# Flexbus_Breakout.net
KiCad netlist of a schematic drawn in EasyEDA Pro
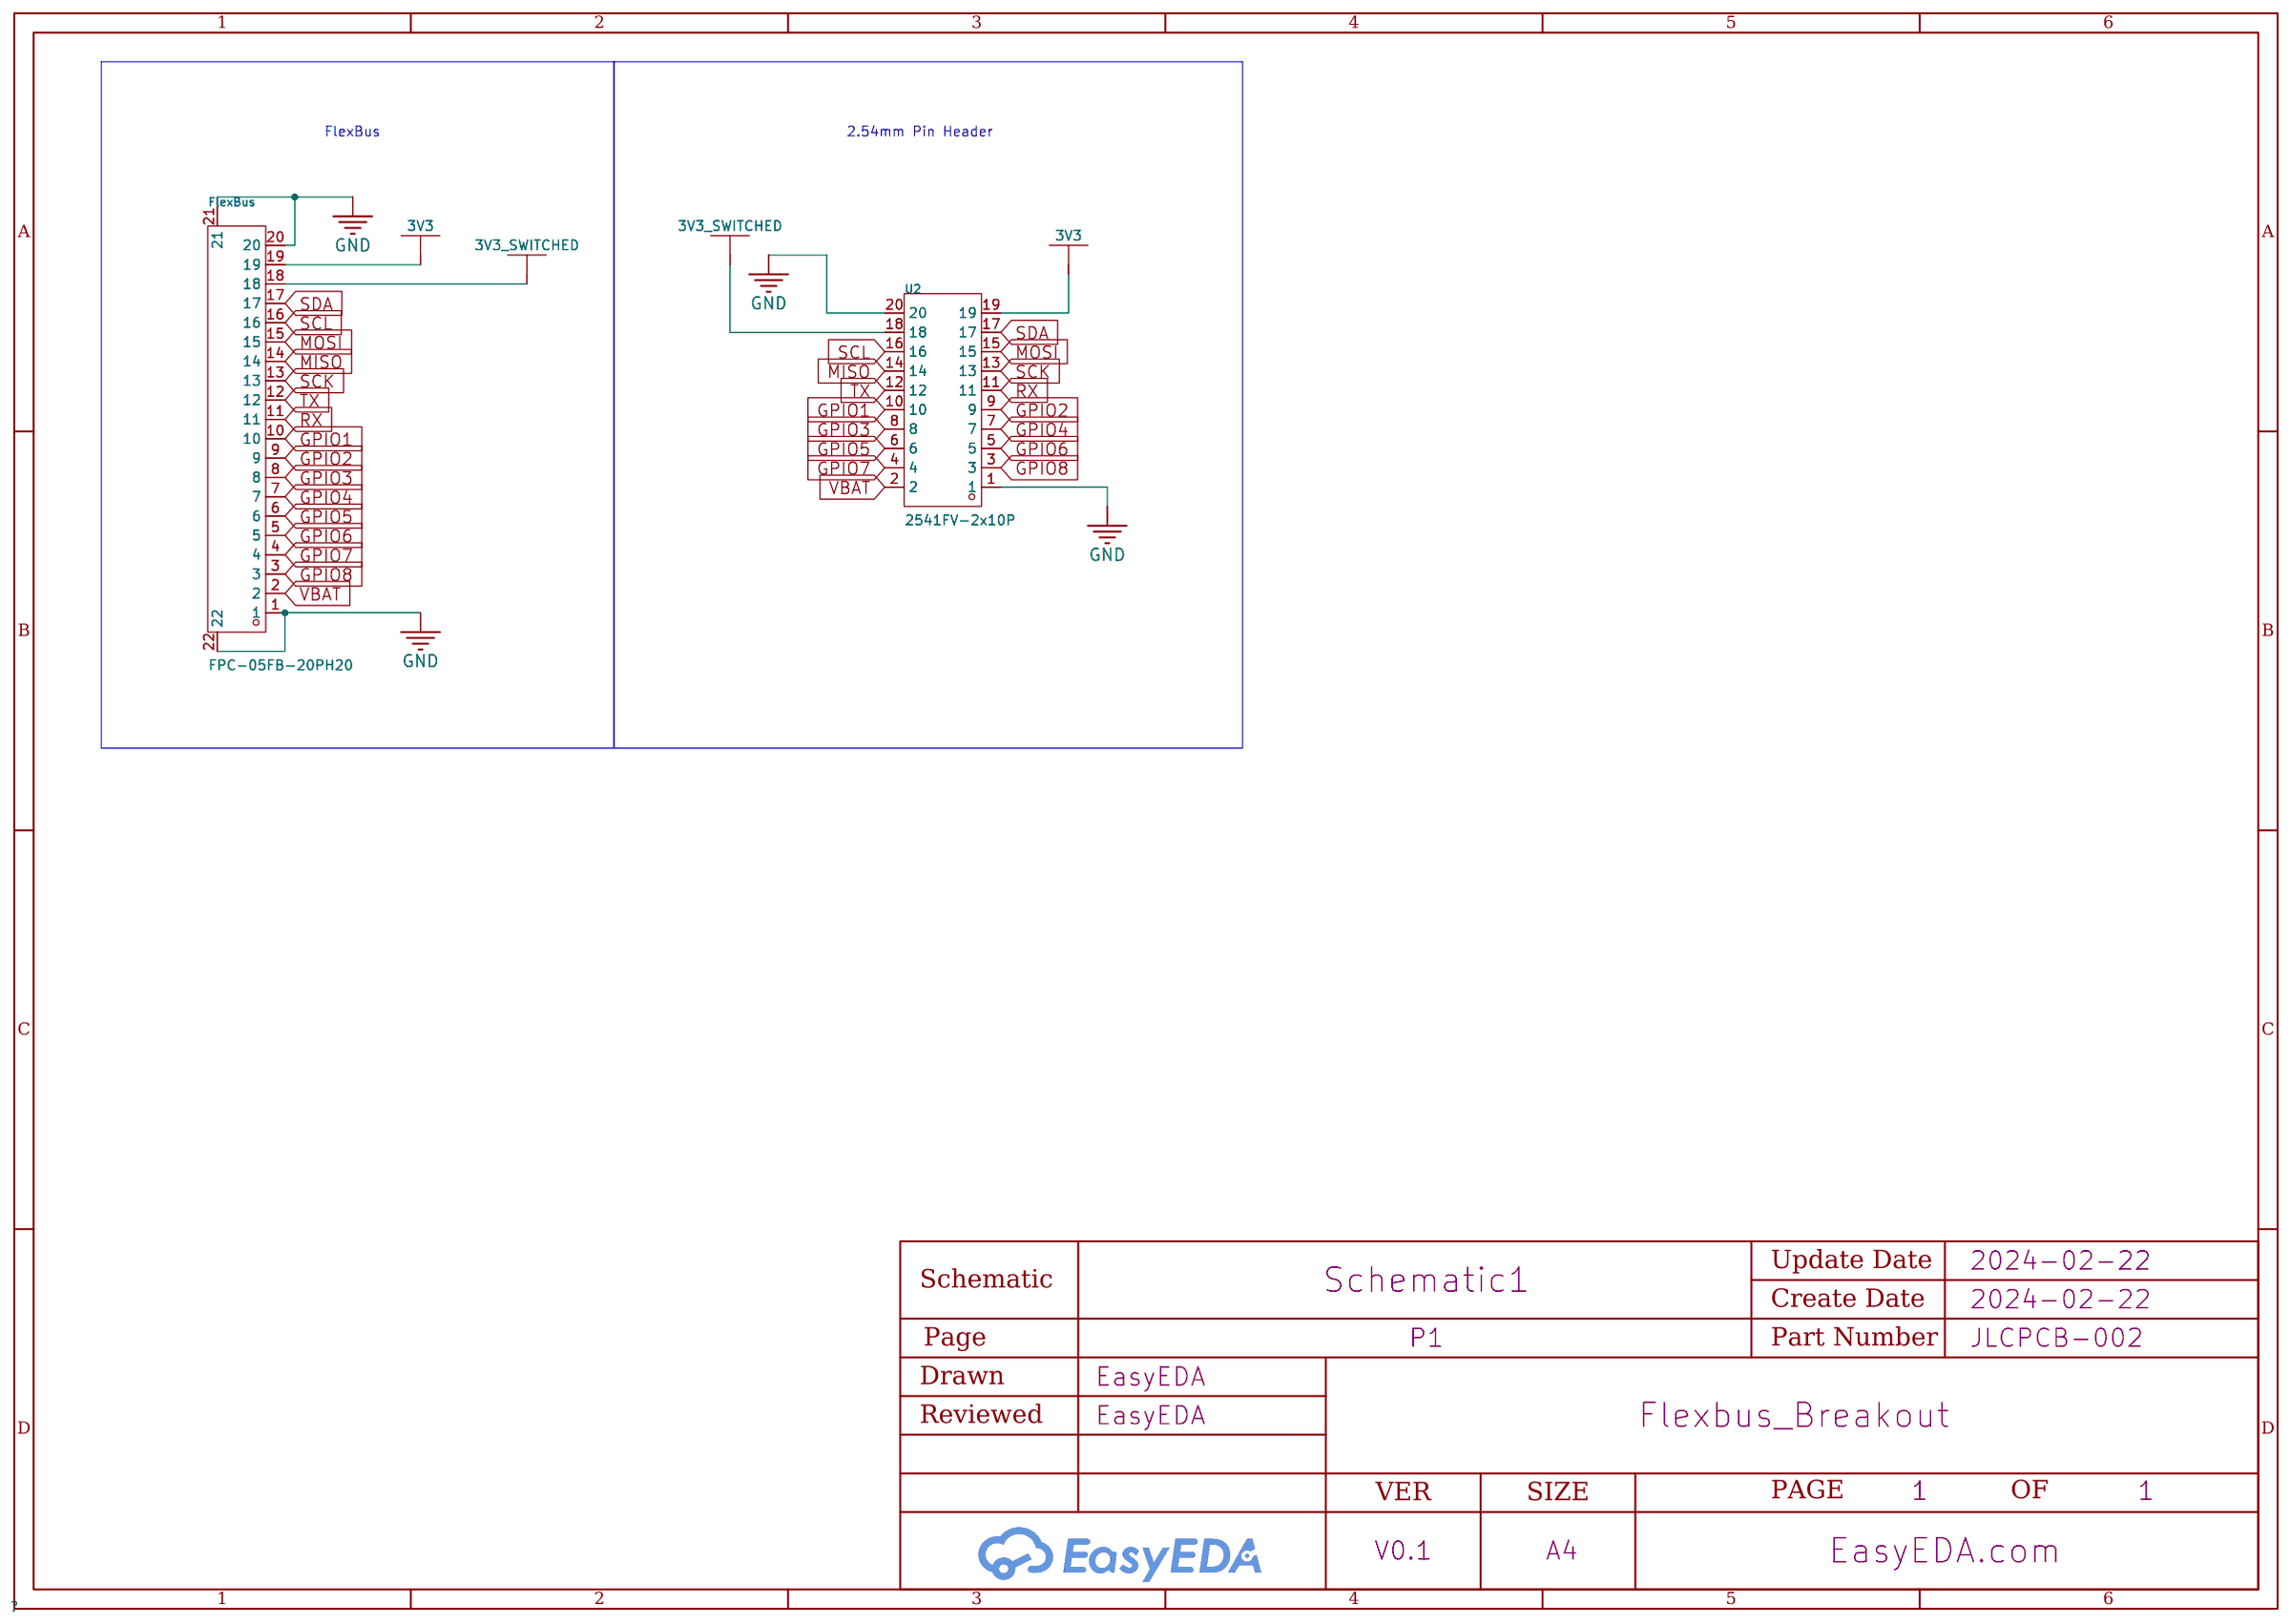
[diagram p0: schematic sheet]

(export (version "E")
  (design (tool "Eeschema 10.0.6"))
  (components
    (comp (ref "FlexBus")
      (value "FPC-05FB-20PH20")
      (footprint "easyedapro:FPC-SMD_20P-P0.50_FPC-05FB-20PH20")
      (fields (field (name "Manufacturer") "XUNPU(讯普)"))
      (libsource (lib "easyedapro") (part "FPC-05FB-20PH20"))
    )
    (comp (ref "U2")
      (value "2541FV-2x10P")
      (footprint "easyedapro:HDR-TH_20P-P2.54-V-F-R2-C10-S2.54")
      (fields (field (name "Manufacturer") "HanElectricity(瀚源)"))
      (libsource (lib "easyedapro") (part "2541FV-2X10P"))
    )
  )
  (nets
    (net (code "1") (name "3V3") (class "Default")
      (node (ref "FlexBus") (pin "19") (pinfunction "19_19") (pintype "input"))
      (node (ref "U2") (pin "19") (pinfunction "19_19") (pintype "input"))
    )
    (net (code "2") (name "3V3_SWITCHED") (class "Default")
      (node (ref "FlexBus") (pin "18") (pinfunction "18_18") (pintype "input"))
      (node (ref "U2") (pin "18") (pinfunction "18_18") (pintype "input"))
    )
    (net (code "3") (name "GND") (class "Default")
      (node (ref "FlexBus") (pin "1") (pinfunction "1_1") (pintype "input"))
      (node (ref "FlexBus") (pin "20") (pinfunction "20_20") (pintype "input"))
      (node (ref "FlexBus") (pin "21") (pinfunction "21_21") (pintype "input"))
      (node (ref "FlexBus") (pin "22") (pinfunction "22_22") (pintype "input"))
      (node (ref "U2") (pin "1") (pinfunction "1_1") (pintype "input"))
      (node (ref "U2") (pin "20") (pinfunction "20_20") (pintype "input"))
    )
    (net (code "4") (name "GPIO1") (class "Default")
      (node (ref "FlexBus") (pin "10") (pinfunction "10_10") (pintype "input"))
      (node (ref "U2") (pin "10") (pinfunction "10_10") (pintype "input"))
    )
    (net (code "5") (name "GPIO2") (class "Default")
      (node (ref "FlexBus") (pin "9") (pinfunction "9_9") (pintype "input"))
      (node (ref "U2") (pin "9") (pinfunction "9_9") (pintype "input"))
    )
    (net (code "6") (name "GPIO3") (class "Default")
      (node (ref "FlexBus") (pin "8") (pinfunction "8_8") (pintype "input"))
      (node (ref "U2") (pin "8") (pinfunction "8_8") (pintype "input"))
    )
    (net (code "7") (name "GPIO4") (class "Default")
      (node (ref "FlexBus") (pin "7") (pinfunction "7_7") (pintype "input"))
      (node (ref "U2") (pin "7") (pinfunction "7_7") (pintype "input"))
    )
    (net (code "8") (name "GPIO5") (class "Default")
      (node (ref "FlexBus") (pin "6") (pinfunction "6_6") (pintype "input"))
      (node (ref "U2") (pin "6") (pinfunction "6_6") (pintype "input"))
    )
    (net (code "9") (name "GPIO6") (class "Default")
      (node (ref "FlexBus") (pin "5") (pinfunction "5_5") (pintype "input"))
      (node (ref "U2") (pin "5") (pinfunction "5_5") (pintype "input"))
    )
    (net (code "10") (name "GPIO7") (class "Default")
      (node (ref "FlexBus") (pin "4") (pinfunction "4_4") (pintype "input"))
      (node (ref "U2") (pin "4") (pinfunction "4_4") (pintype "input"))
    )
    (net (code "11") (name "GPIO8") (class "Default")
      (node (ref "FlexBus") (pin "3") (pinfunction "3_3") (pintype "input"))
      (node (ref "U2") (pin "3") (pinfunction "3_3") (pintype "input"))
    )
    (net (code "12") (name "MISO") (class "Default")
      (node (ref "FlexBus") (pin "14") (pinfunction "14_14") (pintype "input"))
      (node (ref "U2") (pin "14") (pinfunction "14_14") (pintype "input"))
    )
    (net (code "13") (name "MOSI") (class "Default")
      (node (ref "FlexBus") (pin "15") (pinfunction "15_15") (pintype "input"))
      (node (ref "U2") (pin "15") (pinfunction "15_15") (pintype "input"))
    )
    (net (code "14") (name "RX") (class "Default")
      (node (ref "FlexBus") (pin "11") (pinfunction "11_11") (pintype "input"))
      (node (ref "U2") (pin "11") (pinfunction "11_11") (pintype "input"))
    )
    (net (code "15") (name "SCK") (class "Default")
      (node (ref "FlexBus") (pin "13") (pinfunction "13_13") (pintype "input"))
      (node (ref "U2") (pin "13") (pinfunction "13_13") (pintype "input"))
    )
    (net (code "16") (name "SCL") (class "Default")
      (node (ref "FlexBus") (pin "16") (pinfunction "16_16") (pintype "input"))
      (node (ref "U2") (pin "16") (pinfunction "16_16") (pintype "input"))
    )
    (net (code "17") (name "SDA") (class "Default")
      (node (ref "FlexBus") (pin "17") (pinfunction "17_17") (pintype "input"))
      (node (ref "U2") (pin "17") (pinfunction "17_17") (pintype "input"))
    )
    (net (code "18") (name "TX") (class "Default")
      (node (ref "FlexBus") (pin "12") (pinfunction "12_12") (pintype "input"))
      (node (ref "U2") (pin "12") (pinfunction "12_12") (pintype "input"))
    )
    (net (code "19") (name "VBAT") (class "Default")
      (node (ref "FlexBus") (pin "2") (pinfunction "2_2") (pintype "input"))
      (node (ref "U2") (pin "2") (pinfunction "2_2") (pintype "input"))
    )
  )
)
